# EasyEDA_Schematic.net
KiCad netlist of a schematic drawn in EasyEDA
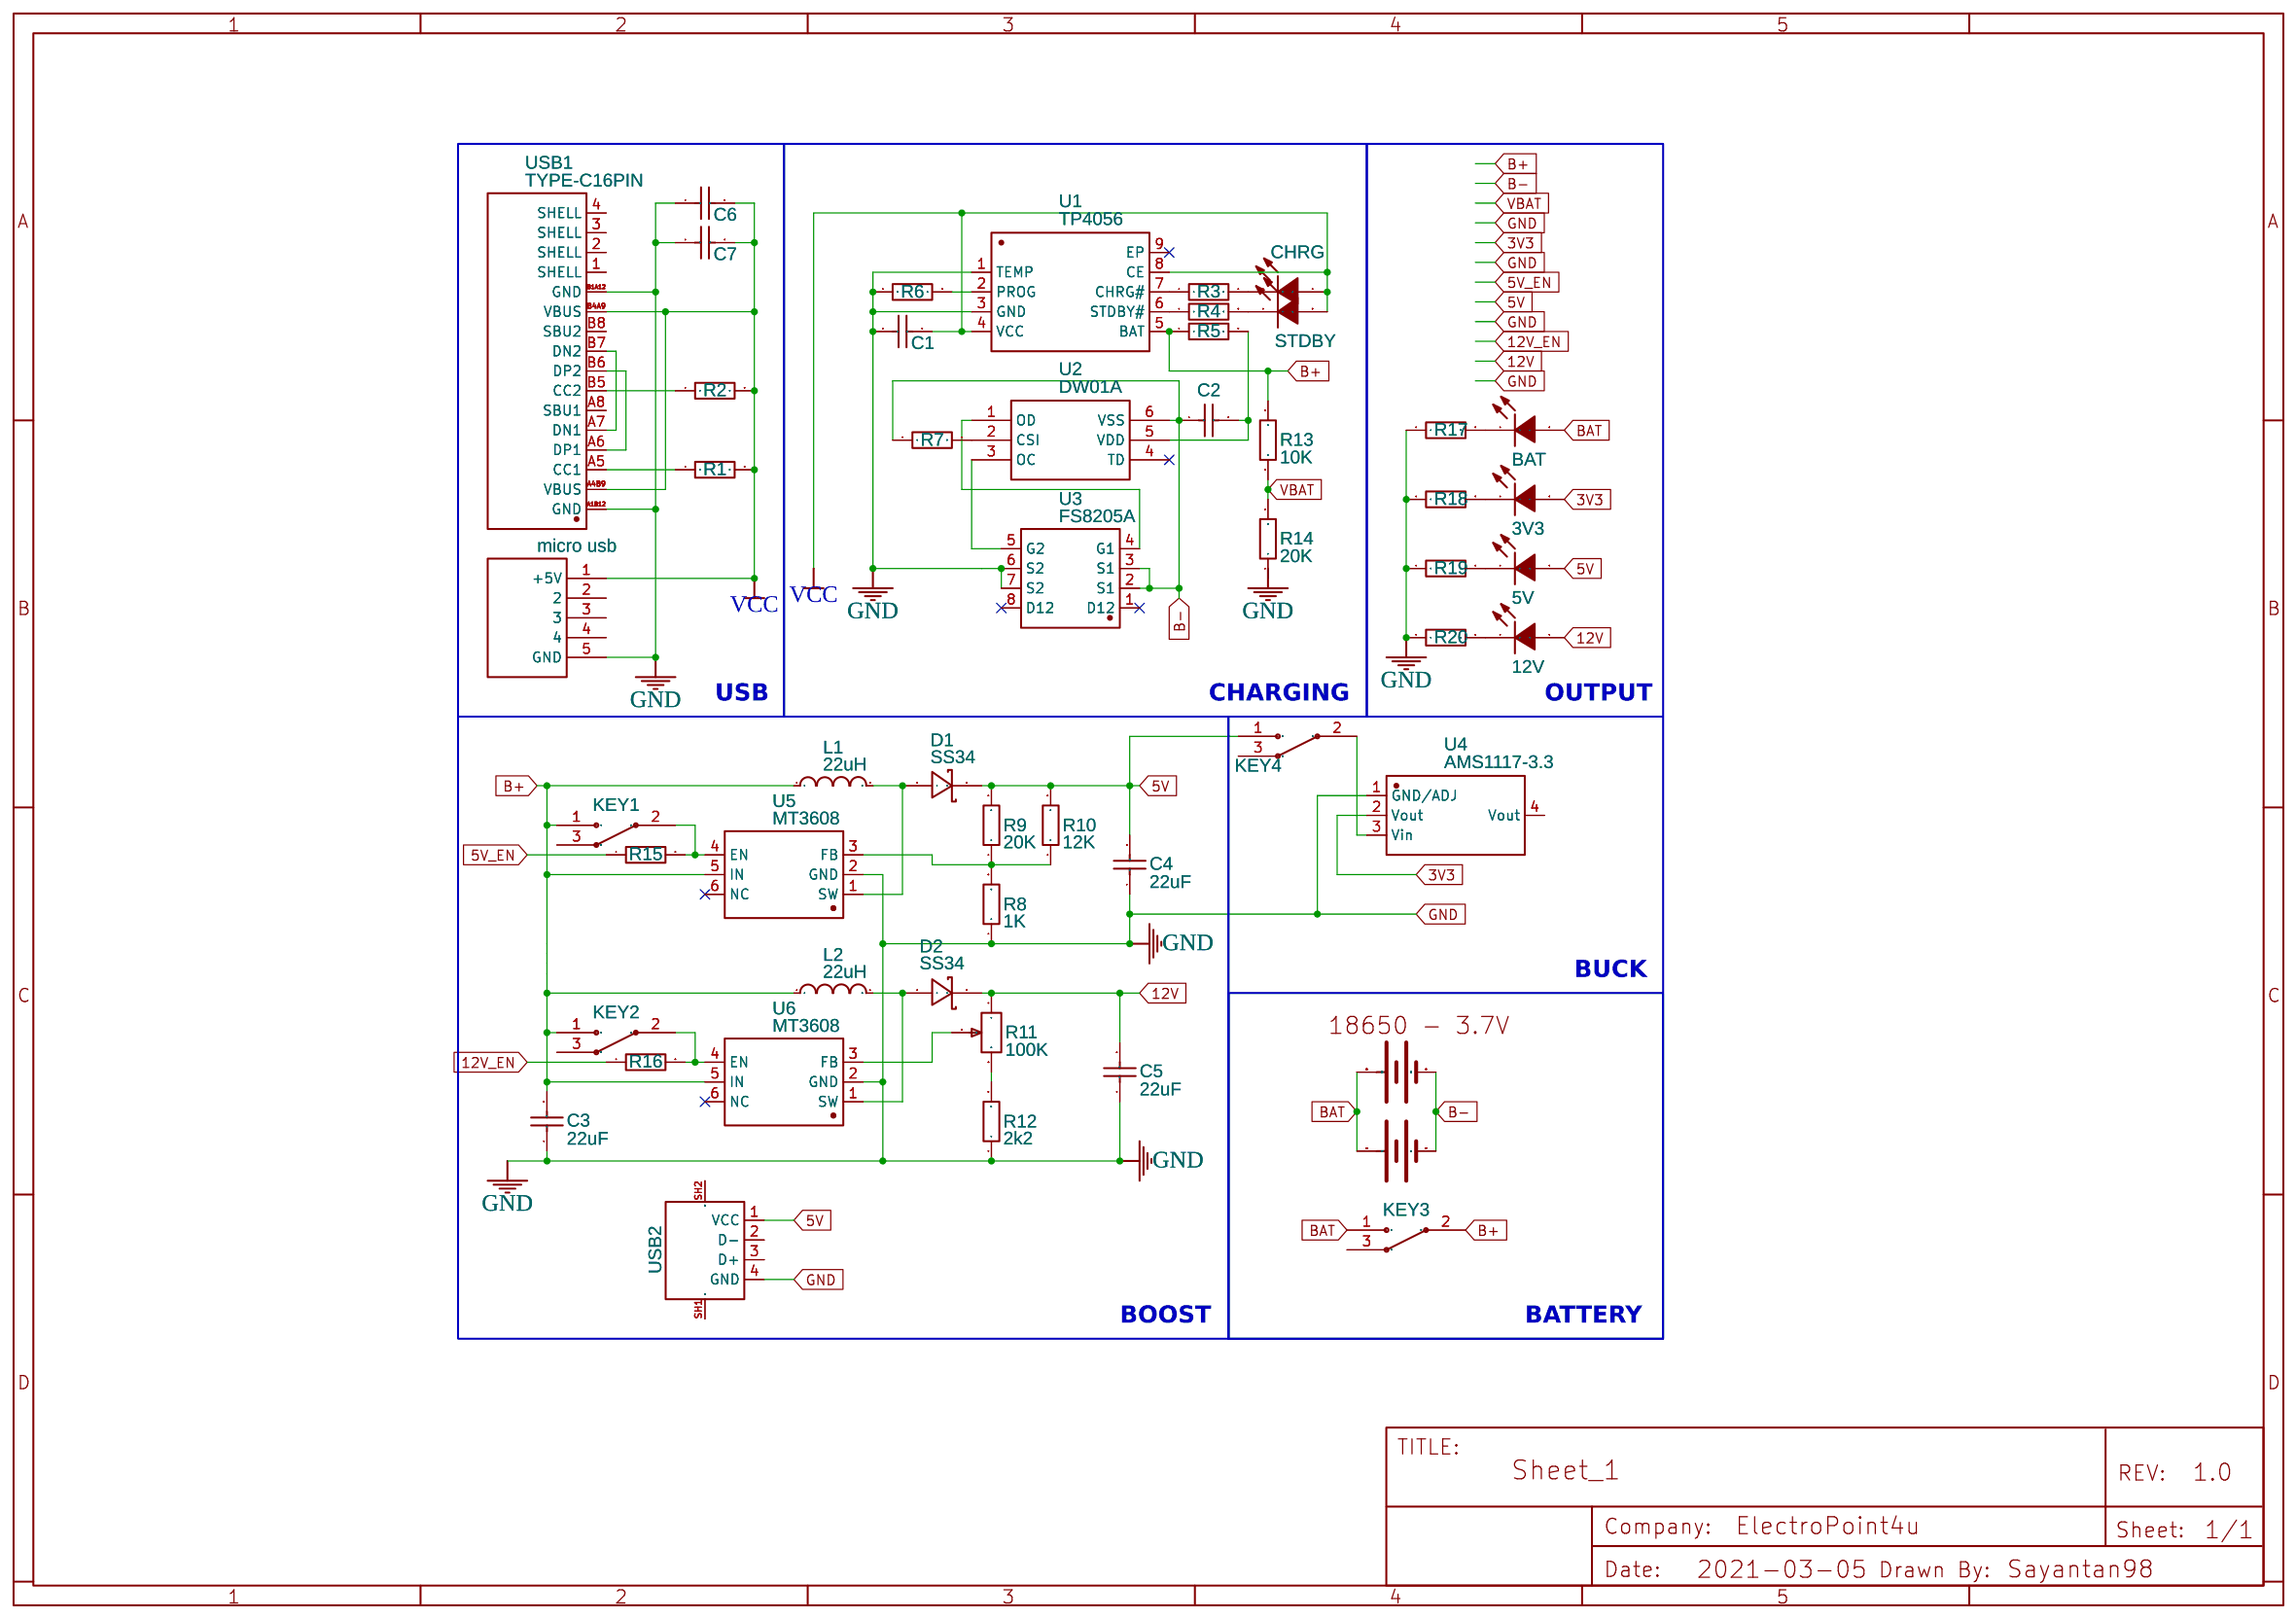
[diagram p0: schematic sheet]

(export (version "E")
  (design (tool "Eeschema 10.0.6"))
  (components
    (comp (ref "3.1V") (value "18650") (libsource (lib "") (part "18650_1")))
    (comp (ref "3.2V") (value "18650") (libsource (lib "") (part "18650")))
    (comp (ref "3V3")
      (value "0805G (Green)")
      (fields (field (name "BOM_Supplier Part") "C2297"))
      (libsource (lib "") (part "0805G (Green)_5"))
    )
    (comp (ref "5V")
      (value "0805G (Green)")
      (fields (field (name "BOM_Supplier Part") "C2297"))
      (libsource (lib "") (part "0805G (Green)_4"))
    )
    (comp (ref "12V")
      (value "0805G (Green)")
      (fields (field (name "BOM_Supplier Part") "C2297"))
      (libsource (lib "") (part "0805G (Green)"))
    )
    (comp (ref "BAT")
      (value "0805G (Green)")
      (fields (field (name "BOM_Supplier Part") "C2297"))
      (libsource (lib "") (part "0805G (Green)_2"))
    )
    (comp (ref "C1")
      (value "10uF")
      (fields
        (field (name "BOM_Manufacturer Part") "CL21A106KAYNNNE")
        (field (name "BOM_Supplier Part") "C15850")
      )
      (libsource (lib "") (part "CL21A106KAYNNNE"))
    )
    (comp (ref "C2")
      (value "100nF")
      (fields
        (field (name "BOM_Manufacturer Part") "CL21B104JBCNNNC")
        (field (name "BOM_Supplier Part") "C62912")
      )
      (libsource (lib "") (part "CL21B104JBCNNNC"))
    )
    (comp (ref "C3")
      (value "22uF")
      (fields
        (field (name "BOM_Manufacturer Part") "CL31A226KPHNNNE")
        (field (name "BOM_Supplier Part") "C5672")
      )
      (libsource (lib "") (part "CL31A226KPHNNNE"))
    )
    (comp (ref "C4")
      (value "22uF")
      (fields
        (field (name "BOM_Manufacturer Part") "CL31A226KPHNNNE")
        (field (name "BOM_Supplier Part") "C5672")
      )
      (libsource (lib "") (part "CL31A226KPHNNNE"))
    )
    (comp (ref "C5")
      (value "22uF")
      (fields
        (field (name "BOM_Manufacturer Part") "CL31A226KPHNNNE")
        (field (name "BOM_Supplier Part") "C5672")
      )
      (libsource (lib "") (part "CL31A226KPHNNNE"))
    )
    (comp (ref "C6")
      (value "10uF")
      (fields
        (field (name "BOM_Manufacturer Part") "CL21A106KAYNNNE")
        (field (name "BOM_Supplier Part") "C15850")
      )
      (libsource (lib "") (part "CL21A106KAYNNNE"))
    )
    (comp (ref "C7")
      (value "1uF")
      (fields
        (field (name "BOM_Manufacturer Part") "CL21A106KAYNNNE")
        (field (name "BOM_Supplier Part") "C15850")
      )
      (libsource (lib "") (part "CL21A106KAYNNNE"))
    )
    (comp (ref "CHRG")
      (value "0805G (Green)")
      (fields (field (name "BOM_Supplier Part") "C2297"))
      (libsource (lib "") (part "0805G (Green)_1"))
    )
    (comp (ref "D1")
      (value "SS34")
      (fields (field (name "BOM_Supplier Part") "C8678"))
      (libsource (lib "") (part "SS34_C8678"))
    )
    (comp (ref "D2")
      (value "SS34")
      (fields (field (name "BOM_Supplier Part") "C8678"))
      (libsource (lib "") (part "SS34_C8678"))
    )
    (comp (ref "KEY1")
      (value "MSK-11027 Toggle Switches")
      (fields (field (name "BOM_Supplier Part") "C21381"))
      (libsource (lib "") (part "MSK-11027 Toggle Switches"))
    )
    (comp (ref "KEY2")
      (value "MSK-11027 Toggle Switches")
      (fields (field (name "BOM_Supplier Part") "C21381"))
      (libsource (lib "") (part "MSK-11027 Toggle Switches"))
    )
    (comp (ref "KEY3")
      (value "MSK-11027 Toggle Switches")
      (fields (field (name "BOM_Supplier Part") "C21381"))
      (libsource (lib "") (part "MSK-11027 Toggle Switches"))
    )
    (comp (ref "KEY4")
      (value "MSK-11027 Toggle Switches")
      (fields (field (name "BOM_Supplier Part") "C21381"))
      (libsource (lib "") (part "MSK-11027 Toggle Switches"))
    )
    (comp (ref "L1")
      (value "22uH")
      (fields
        (field (name "BOM_Manufacturer Part") "SWRB1205S-220MT")
        (field (name "BOM_Supplier Part") "C169385")
      )
      (libsource (lib "") (part "SWRB1205S-220MT"))
    )
    (comp (ref "L2")
      (value "22uH")
      (fields
        (field (name "BOM_Manufacturer Part") "SWRB1205S-220MT")
        (field (name "BOM_Supplier Part") "C169385")
      )
      (libsource (lib "") (part "SWRB1205S-220MT"))
    )
    (comp (ref "R1")
      (value "5.1K")
      (fields
        (field (name "BOM_Manufacturer Part") "0805W8F5101T5E")
        (field (name "BOM_Supplier Part") "C27834")
      )
      (libsource (lib "") (part "0805W8F5101T5E"))
    )
    (comp (ref "R2")
      (value "5.1K")
      (fields
        (field (name "BOM_Manufacturer Part") "0805W8F5101T5E")
        (field (name "BOM_Supplier Part") "C27834")
      )
      (libsource (lib "") (part "0805W8F5101T5E"))
    )
    (comp (ref "R3")
      (value "1K")
      (fields
        (field (name "BOM_Manufacturer Part") "0805WAD1001T5E")
        (field (name "BOM_Supplier Part") "C169072")
      )
      (libsource (lib "") (part "0805WAD1001T5E"))
    )
    (comp (ref "R4")
      (value "1K")
      (fields
        (field (name "BOM_Manufacturer Part") "0805WAD1001T5E")
        (field (name "BOM_Supplier Part") "C169072")
      )
      (libsource (lib "") (part "0805WAD1001T5E"))
    )
    (comp (ref "R5")
      (value "100")
      (fields
        (field (name "BOM_Manufacturer Part") "0805W8F1000T5E")
        (field (name "BOM_Supplier Part") "C17408")
      )
      (libsource (lib "") (part "0805W8F1000T5E"))
    )
    (comp (ref "R6")
      (value "2K")
      (fields
        (field (name "BOM_Manufacturer Part") "0805W8F2001T5E")
        (field (name "BOM_Supplier Part") "C17604")
      )
      (libsource (lib "") (part "0805W8F2001T5E"))
    )
    (comp (ref "R7")
      (value "1K")
      (fields
        (field (name "BOM_Manufacturer Part") "0805WAD1001T5E")
        (field (name "BOM_Supplier Part") "C169072")
      )
      (libsource (lib "") (part "0805WAD1001T5E"))
    )
    (comp (ref "R8")
      (value "1K")
      (fields
        (field (name "BOM_Manufacturer Part") "0805W8F1001T5E")
        (field (name "BOM_Supplier Part") "C17513")
      )
      (libsource (lib "") (part "0805W8F1001T5E"))
    )
    (comp (ref "R9")
      (value "20K")
      (fields
        (field (name "BOM_Manufacturer Part") "0805W8F2002T5E")
        (field (name "BOM_Supplier Part") "C4328")
      )
      (libsource (lib "") (part "0805W8F2002T5E"))
    )
    (comp (ref "R10")
      (value "12K")
      (fields
        (field (name "BOM_Manufacturer Part") "0805W8F1202T5E")
        (field (name "BOM_Supplier Part") "C17444")
      )
      (libsource (lib "") (part "0805W8F1202T5E"))
    )
    (comp (ref "R11") (value "100K") (libsource (lib "") (part "POTENTIOMETER VARIABLE RESISTOR")))
    (comp (ref "R12")
      (value "2k2")
      (fields
        (field (name "BOM_Manufacturer Part") "0805W8F1001T5E")
        (field (name "BOM_Supplier Part") "C17513")
      )
      (libsource (lib "") (part "0805W8F1001T5E"))
    )
    (comp (ref "R13")
      (value "10K")
      (fields
        (field (name "BOM_Manufacturer Part") "TC0550B1002T5E")
        (field (name "BOM_Supplier Part") "C141888")
      )
      (libsource (lib "") (part "TC0550B1002T5E"))
    )
    (comp (ref "R14")
      (value "20K")
      (fields
        (field (name "BOM_Manufacturer Part") "TC0550B1002T5E")
        (field (name "BOM_Supplier Part") "C141888")
      )
      (libsource (lib "") (part "TC0550B1002T5E"))
    )
    (comp (ref "R15")
      (value "100")
      (fields
        (field (name "BOM_Manufacturer Part") "0805W8F1000T5E")
        (field (name "BOM_Supplier Part") "C17408")
      )
      (libsource (lib "") (part "0805W8F1000T5E"))
    )
    (comp (ref "R16")
      (value "100")
      (fields
        (field (name "BOM_Manufacturer Part") "0805W8F1000T5E")
        (field (name "BOM_Supplier Part") "C17408")
      )
      (libsource (lib "") (part "0805W8F1000T5E"))
    )
    (comp (ref "R17")
      (value "1K")
      (fields
        (field (name "BOM_Manufacturer Part") "0805WAD1001T5E")
        (field (name "BOM_Supplier Part") "C169072")
      )
      (libsource (lib "") (part "0805WAD1001T5E"))
    )
    (comp (ref "R18")
      (value "1K")
      (fields
        (field (name "BOM_Manufacturer Part") "0805WAD1001T5E")
        (field (name "BOM_Supplier Part") "C169072")
      )
      (libsource (lib "") (part "0805WAD1001T5E"))
    )
    (comp (ref "R19")
      (value "1K")
      (fields
        (field (name "BOM_Manufacturer Part") "0805WAD1001T5E")
        (field (name "BOM_Supplier Part") "C169072")
      )
      (libsource (lib "") (part "0805WAD1001T5E"))
    )
    (comp (ref "R20")
      (value "1K")
      (fields
        (field (name "BOM_Manufacturer Part") "0805WAD1001T5E")
        (field (name "BOM_Supplier Part") "C169072")
      )
      (libsource (lib "") (part "0805WAD1001T5E"))
    )
    (comp (ref "STDBY")
      (value "0805G (Green)")
      (fields (field (name "BOM_Supplier Part") "C2297"))
      (libsource (lib "") (part "0805G (Green)_3"))
    )
    (comp (ref "U1")
      (value "TP4056")
      (fields (field (name "BOM_Supplier Part") "C382139"))
      (libsource (lib "") (part "TP4056_C382139"))
    )
    (comp (ref "U2")
      (value "DW01A")
      (fields (field (name "BOM_Supplier Part") "C85680"))
      (libsource (lib "") (part "DW01A"))
    )
    (comp (ref "U3")
      (value "FS8205A")
      (fields (field (name "BOM_Supplier Part") "C16052"))
      (libsource (lib "") (part "FS8205A"))
    )
    (comp (ref "U4")
      (value "AMS1117-3.3")
      (fields (field (name "BOM_Supplier Part") "C6186"))
      (libsource (lib "") (part "AMS1117-3.3"))
    )
    (comp (ref "U5")
      (value "MT3608")
      (fields (field (name "BOM_Supplier Part") "C84817"))
      (libsource (lib "") (part "MT3608"))
    )
    (comp (ref "U6")
      (value "MT3608")
      (fields (field (name "BOM_Supplier Part") "C84817"))
      (libsource (lib "") (part "MT3608"))
    )
    (comp (ref "USB1")
      (value "TYPE-C16PIN")
      (fields (field (name "BOM_Supplier Part") "C393939"))
      (libsource (lib "") (part "TYPE-C16PIN"))
    )
    (comp (ref "USB2")
      (value "JTJ-USB-AF-08")
      (fields (field (name "BOM_Supplier Part") "C2345"))
      (libsource (lib "") (part "JTJ-USB-AF-08"))
    )
    (comp (ref "USB3") (value "micro usb") (libsource (lib "") (part "micro usb")))
  )
  (nets
    (net (code "1") (name "3V3") (class "Default")
      (node (ref "3V3") (pin "2") (pinfunction "A_2") (pintype "unspecified"))
      (node (ref "U4") (pin "2") (pinfunction "Vout_2") (pintype "unspecified"))
    )
    (net (code "2") (name "5V") (class "Default")
      (node (ref "5V") (pin "2") (pinfunction "A_2") (pintype "unspecified"))
      (node (ref "C4") (pin "2") (pinfunction "2_2") (pintype "input"))
      (node (ref "D1") (pin "1") (pinfunction "K_1") (pintype "unspecified"))
      (node (ref "KEY4") (pin "1") (pinfunction "1_1") (pintype "unspecified"))
      (node (ref "R10") (pin "2") (pinfunction "2_2") (pintype "input"))
      (node (ref "R9") (pin "2") (pinfunction "2_2") (pintype "input"))
      (node (ref "USB2") (pin "1") (pinfunction "VCC_1") (pintype "input"))
    )
    (net (code "3") (name "5V_EN") (class "Default")
      (node (ref "R15") (pin "1") (pinfunction "1_1") (pintype "input"))
    )
    (net (code "4") (name "12V") (class "Default")
      (node (ref "12V") (pin "2") (pinfunction "A_2") (pintype "unspecified"))
      (node (ref "C5") (pin "2") (pinfunction "2_2") (pintype "input"))
      (node (ref "D2") (pin "1") (pinfunction "K_1") (pintype "unspecified"))
      (node (ref "R11") (pin "1") (pinfunction "1_1") (pintype "input"))
    )
    (net (code "5") (name "12V_EN") (class "Default")
      (node (ref "R16") (pin "1") (pinfunction "1_1") (pintype "input"))
    )
    (net (code "6") (name "B+") (class "Default")
      (node (ref "C3") (pin "2") (pinfunction "2_2") (pintype "input"))
      (node (ref "KEY1") (pin "1") (pinfunction "1_1") (pintype "unspecified"))
      (node (ref "KEY2") (pin "1") (pinfunction "1_1") (pintype "unspecified"))
      (node (ref "KEY3") (pin "2") (pinfunction "2_2") (pintype "unspecified"))
      (node (ref "L1") (pin "1") (pinfunction "1_1") (pintype "unspecified"))
      (node (ref "L2") (pin "1") (pinfunction "1_1") (pintype "unspecified"))
      (node (ref "R13") (pin "2") (pinfunction "2_2") (pintype "unspecified"))
      (node (ref "R5") (pin "1") (pinfunction "1_1") (pintype "input"))
      (node (ref "U1") (pin "5") (pinfunction "BAT_5") (pintype "unspecified"))
      (node (ref "U5") (pin "5") (pinfunction "IN_5") (pintype "unspecified"))
      (node (ref "U6") (pin "5") (pinfunction "IN_5") (pintype "unspecified"))
    )
    (net (code "7") (name "B-") (class "Default")
      (node (ref "3.1V") (pin "GND") (pinfunction "GND_GND") (pintype "passive"))
      (node (ref "3.2V") (pin "GND") (pinfunction "GND_GND") (pintype "passive"))
      (node (ref "C2") (pin "1") (pinfunction "1_1") (pintype "input"))
      (node (ref "R7") (pin "1") (pinfunction "1_1") (pintype "unspecified"))
      (node (ref "U2") (pin "6") (pinfunction "VSS_6") (pintype "unspecified"))
      (node (ref "U3") (pin "2") (pinfunction "S1_2") (pintype "unspecified"))
      (node (ref "U3") (pin "3") (pinfunction "S1_3") (pintype "unspecified"))
    )
    (net (code "8") (name "BAT") (class "Default")
      (node (ref "3.1V") (pin "Positive") (pinfunction "Positive_Positive") (pintype "passive"))
      (node (ref "3.2V") (pin "Positive") (pinfunction "Positive_Positive") (pintype "passive"))
      (node (ref "BAT") (pin "2") (pinfunction "A_2") (pintype "unspecified"))
      (node (ref "KEY3") (pin "1") (pinfunction "1_1") (pintype "unspecified"))
    )
    (net (code "9") (name "GND") (class "Default")
      (node (ref "C1") (pin "1") (pinfunction "1_1") (pintype "input"))
      (node (ref "C3") (pin "1") (pinfunction "1_1") (pintype "input"))
      (node (ref "C4") (pin "1") (pinfunction "1_1") (pintype "input"))
      (node (ref "C5") (pin "1") (pinfunction "1_1") (pintype "input"))
      (node (ref "C6") (pin "1") (pinfunction "1_1") (pintype "input"))
      (node (ref "C7") (pin "1") (pinfunction "1_1") (pintype "input"))
      (node (ref "R12") (pin "1") (pinfunction "1_1") (pintype "input"))
      (node (ref "R14") (pin "1") (pinfunction "1_1") (pintype "unspecified"))
      (node (ref "R17") (pin "1") (pinfunction "1_1") (pintype "unspecified"))
      (node (ref "R18") (pin "1") (pinfunction "1_1") (pintype "unspecified"))
      (node (ref "R19") (pin "1") (pinfunction "1_1") (pintype "unspecified"))
      (node (ref "R20") (pin "1") (pinfunction "1_1") (pintype "unspecified"))
      (node (ref "R6") (pin "1") (pinfunction "1_1") (pintype "input"))
      (node (ref "R8") (pin "1") (pinfunction "1_1") (pintype "input"))
      (node (ref "U1") (pin "1") (pinfunction "TEMP_1") (pintype "unspecified"))
      (node (ref "U1") (pin "3") (pinfunction "GND_3") (pintype "unspecified"))
      (node (ref "U3") (pin "6") (pinfunction "S2_6") (pintype "unspecified"))
      (node (ref "U3") (pin "7") (pinfunction "S2_7") (pintype "unspecified"))
      (node (ref "U4") (pin "1") (pinfunction "GND/ADJ_1") (pintype "unspecified"))
      (node (ref "U5") (pin "2") (pinfunction "GND_2") (pintype "unspecified"))
      (node (ref "U6") (pin "2") (pinfunction "GND_2") (pintype "unspecified"))
      (node (ref "USB1") (pin "A1B12") (pinfunction "GND_A1B12") (pintype "unspecified"))
      (node (ref "USB1") (pin "B1A12") (pinfunction "GND_B1A12") (pintype "unspecified"))
      (node (ref "USB2") (pin "4") (pinfunction "GND_4") (pintype "input"))
      (node (ref "USB3") (pin "5") (pinfunction "GND_5") (pintype "unspecified"))
    )
    (net (code "10") (name "Net-(3V3-K)") (class "Default")
      (node (ref "3V3") (pin "1") (pinfunction "K_1") (pintype "unspecified"))
      (node (ref "R18") (pin "2") (pinfunction "2_2") (pintype "unspecified"))
    )
    (net (code "11") (name "Net-(5V-K)") (class "Default")
      (node (ref "5V") (pin "1") (pinfunction "K_1") (pintype "unspecified"))
      (node (ref "R19") (pin "2") (pinfunction "2_2") (pintype "unspecified"))
    )
    (net (code "12") (name "Net-(12V-K)") (class "Default")
      (node (ref "12V") (pin "1") (pinfunction "K_1") (pintype "unspecified"))
      (node (ref "R20") (pin "2") (pinfunction "2_2") (pintype "unspecified"))
    )
    (net (code "13") (name "Net-(BAT-K)") (class "Default")
      (node (ref "BAT") (pin "1") (pinfunction "K_1") (pintype "unspecified"))
      (node (ref "R17") (pin "2") (pinfunction "2_2") (pintype "unspecified"))
    )
    (net (code "14") (name "Net-(CHRG-K)") (class "Default")
      (node (ref "CHRG") (pin "1") (pinfunction "K_1") (pintype "unspecified"))
      (node (ref "R3") (pin "2") (pinfunction "2_2") (pintype "unspecified"))
    )
    (net (code "15") (name "Net-(D1-A)") (class "Default")
      (node (ref "D1") (pin "2") (pinfunction "A_2") (pintype "unspecified"))
      (node (ref "L1") (pin "2") (pinfunction "2_2") (pintype "unspecified"))
      (node (ref "U5") (pin "1") (pinfunction "SW_1") (pintype "unspecified"))
    )
    (net (code "16") (name "Net-(D2-A)") (class "Default")
      (node (ref "D2") (pin "2") (pinfunction "A_2") (pintype "unspecified"))
      (node (ref "L2") (pin "2") (pinfunction "2_2") (pintype "unspecified"))
      (node (ref "U6") (pin "1") (pinfunction "SW_1") (pintype "unspecified"))
    )
    (net (code "17") (name "Net-(R11-Pad3)") (class "Default")
      (node (ref "R11") (pin "3") (pinfunction "3_3") (pintype "input"))
      (node (ref "R12") (pin "2") (pinfunction "2_2") (pintype "input"))
    )
    (net (code "18") (name "Net-(STDBY-K)") (class "Default")
      (node (ref "R4") (pin "2") (pinfunction "2_2") (pintype "unspecified"))
      (node (ref "STDBY") (pin "1") (pinfunction "K_1") (pintype "unspecified"))
    )
    (net (code "19") (name "Net-(U1-CHRG#)") (class "Default")
      (node (ref "R3") (pin "1") (pinfunction "1_1") (pintype "unspecified"))
      (node (ref "U1") (pin "7") (pinfunction "CHRG#_7") (pintype "unspecified"))
    )
    (net (code "20") (name "Net-(U1-PROG)") (class "Default")
      (node (ref "R6") (pin "2") (pinfunction "2_2") (pintype "input"))
      (node (ref "U1") (pin "2") (pinfunction "PROG_2") (pintype "unspecified"))
    )
    (net (code "21") (name "Net-(U1-STDBY#)") (class "Default")
      (node (ref "R4") (pin "1") (pinfunction "1_1") (pintype "unspecified"))
      (node (ref "U1") (pin "6") (pinfunction "STDBY#_6") (pintype "unspecified"))
    )
    (net (code "22") (name "Net-(U2-CSI)") (class "Default")
      (node (ref "R7") (pin "2") (pinfunction "2_2") (pintype "unspecified"))
      (node (ref "U2") (pin "2") (pinfunction "CSI_2") (pintype "unspecified"))
    )
    (net (code "23") (name "Net-(U2-OC)") (class "Default")
      (node (ref "U2") (pin "3") (pinfunction "OC_3") (pintype "unspecified"))
      (node (ref "U3") (pin "5") (pinfunction "G2_5") (pintype "unspecified"))
    )
    (net (code "24") (name "Net-(U2-OD)") (class "Default")
      (node (ref "U2") (pin "1") (pinfunction "OD_1") (pintype "unspecified"))
      (node (ref "U3") (pin "4") (pinfunction "G1_4") (pintype "unspecified"))
    )
    (net (code "25") (name "Net-(U2-VDD)") (class "Default")
      (node (ref "C2") (pin "2") (pinfunction "2_2") (pintype "input"))
      (node (ref "R5") (pin "2") (pinfunction "2_2") (pintype "input"))
      (node (ref "U2") (pin "5") (pinfunction "VDD_5") (pintype "unspecified"))
    )
    (net (code "26") (name "Net-(U4-Vin)") (class "Default")
      (node (ref "KEY4") (pin "2") (pinfunction "2_2") (pintype "unspecified"))
      (node (ref "U4") (pin "3") (pinfunction "Vin_3") (pintype "unspecified"))
    )
    (net (code "27") (name "Net-(U5-EN)") (class "Default")
      (node (ref "KEY1") (pin "2") (pinfunction "2_2") (pintype "unspecified"))
      (node (ref "R15") (pin "2") (pinfunction "2_2") (pintype "input"))
      (node (ref "U5") (pin "4") (pinfunction "EN_4") (pintype "unspecified"))
    )
    (net (code "28") (name "Net-(U5-FB)") (class "Default")
      (node (ref "R10") (pin "1") (pinfunction "1_1") (pintype "input"))
      (node (ref "R8") (pin "2") (pinfunction "2_2") (pintype "input"))
      (node (ref "R9") (pin "1") (pinfunction "1_1") (pintype "input"))
      (node (ref "U5") (pin "3") (pinfunction "FB_3") (pintype "unspecified"))
    )
    (net (code "29") (name "Net-(U6-EN)") (class "Default")
      (node (ref "KEY2") (pin "2") (pinfunction "2_2") (pintype "unspecified"))
      (node (ref "R16") (pin "2") (pinfunction "2_2") (pintype "input"))
      (node (ref "U6") (pin "4") (pinfunction "EN_4") (pintype "unspecified"))
    )
    (net (code "30") (name "Net-(U6-FB)") (class "Default")
      (node (ref "R11") (pin "2") (pinfunction "2_2") (pintype "input"))
      (node (ref "U6") (pin "3") (pinfunction "FB_3") (pintype "unspecified"))
    )
    (net (code "31") (name "Net-(USB1-CC1)") (class "Default")
      (node (ref "R1") (pin "1") (pinfunction "1_1") (pintype "input"))
      (node (ref "USB1") (pin "A5") (pinfunction "CC1_A5") (pintype "unspecified"))
    )
    (net (code "32") (name "Net-(USB1-CC2)") (class "Default")
      (node (ref "R2") (pin "1") (pinfunction "1_1") (pintype "input"))
      (node (ref "USB1") (pin "B5") (pinfunction "CC2_B5") (pintype "unspecified"))
    )
    (net (code "33") (name "Net-(USB1-DN1)") (class "Default")
      (node (ref "USB1") (pin "A7") (pinfunction "DN1_A7") (pintype "unspecified"))
      (node (ref "USB1") (pin "B7") (pinfunction "DN2_B7") (pintype "unspecified"))
    )
    (net (code "34") (name "Net-(USB1-DP1)") (class "Default")
      (node (ref "USB1") (pin "A6") (pinfunction "DP1_A6") (pintype "unspecified"))
      (node (ref "USB1") (pin "B6") (pinfunction "DP2_B6") (pintype "unspecified"))
    )
    (net (code "35") (name "VBAT") (class "Default")
      (node (ref "R13") (pin "1") (pinfunction "1_1") (pintype "unspecified"))
      (node (ref "R14") (pin "2") (pinfunction "2_2") (pintype "unspecified"))
    )
    (net (code "36") (name "VCC") (class "Default")
      (node (ref "C1") (pin "2") (pinfunction "2_2") (pintype "input"))
      (node (ref "C6") (pin "2") (pinfunction "2_2") (pintype "input"))
      (node (ref "C7") (pin "2") (pinfunction "2_2") (pintype "input"))
      (node (ref "CHRG") (pin "2") (pinfunction "A_2") (pintype "unspecified"))
      (node (ref "R1") (pin "2") (pinfunction "2_2") (pintype "input"))
      (node (ref "R2") (pin "2") (pinfunction "2_2") (pintype "input"))
      (node (ref "STDBY") (pin "2") (pinfunction "A_2") (pintype "unspecified"))
      (node (ref "U1") (pin "4") (pinfunction "VCC_4") (pintype "unspecified"))
      (node (ref "U1") (pin "8") (pinfunction "CE_8") (pintype "unspecified"))
      (node (ref "USB1") (pin "A4B9") (pinfunction "VBUS_A4B9") (pintype "unspecified"))
      (node (ref "USB1") (pin "B4A9") (pinfunction "VBUS_B4A9") (pintype "unspecified"))
      (node (ref "USB3") (pin "1") (pinfunction "+5V_1") (pintype "unspecified"))
    )
    (net (code "37") (name "unconnected-(KEY1-Pad3)") (class "Default")
      (node (ref "KEY1") (pin "3") (pinfunction "3_3") (pintype "unspecified"))
    )
    (net (code "38") (name "unconnected-(KEY2-Pad3)") (class "Default")
      (node (ref "KEY2") (pin "3") (pinfunction "3_3") (pintype "unspecified"))
    )
    (net (code "39") (name "unconnected-(KEY3-Pad3)") (class "Default")
      (node (ref "KEY3") (pin "3") (pinfunction "3_3") (pintype "unspecified"))
    )
    (net (code "40") (name "unconnected-(KEY4-Pad3)") (class "Default")
      (node (ref "KEY4") (pin "3") (pinfunction "3_3") (pintype "unspecified"))
    )
    (net (code "41") (name "unconnected-(U1-EP-Pad9)") (class "Default")
      (node (ref "U1") (pin "9") (pinfunction "EP_9") (pintype "unspecified+no_connect"))
    )
    (net (code "42") (name "unconnected-(U2-TD-Pad4)") (class "Default")
      (node (ref "U2") (pin "4") (pinfunction "TD_4") (pintype "unspecified+no_connect"))
    )
    (net (code "43") (name "unconnected-(U3-D12-Pad1)") (class "Default")
      (node (ref "U3") (pin "1") (pinfunction "D12_1") (pintype "unspecified+no_connect"))
    )
    (net (code "44") (name "unconnected-(U3-D12-Pad8)") (class "Default")
      (node (ref "U3") (pin "8") (pinfunction "D12_8") (pintype "unspecified+no_connect"))
    )
    (net (code "45") (name "unconnected-(U4-Vout-Pad4)") (class "Default")
      (node (ref "U4") (pin "4") (pinfunction "Vout_4") (pintype "unspecified"))
    )
    (net (code "46") (name "unconnected-(U5-NC-Pad6)") (class "Default")
      (node (ref "U5") (pin "6") (pinfunction "NC_6") (pintype "unspecified+no_connect"))
    )
    (net (code "47") (name "unconnected-(U6-NC-Pad6)") (class "Default")
      (node (ref "U6") (pin "6") (pinfunction "NC_6") (pintype "unspecified+no_connect"))
    )
    (net (code "48") (name "unconnected-(USB1-SBU1-PadA8)") (class "Default")
      (node (ref "USB1") (pin "A8") (pinfunction "SBU1_A8") (pintype "unspecified"))
    )
    (net (code "49") (name "unconnected-(USB1-SBU2-PadB8)") (class "Default")
      (node (ref "USB1") (pin "B8") (pinfunction "SBU2_B8") (pintype "unspecified"))
    )
    (net (code "50") (name "unconnected-(USB1-SHELL-Pad1)") (class "Default")
      (node (ref "USB1") (pin "1") (pinfunction "SHELL_1") (pintype "unspecified"))
    )
    (net (code "51") (name "unconnected-(USB1-SHELL-Pad2)") (class "Default")
      (node (ref "USB1") (pin "2") (pinfunction "SHELL_2") (pintype "unspecified"))
    )
    (net (code "52") (name "unconnected-(USB1-SHELL-Pad3)") (class "Default")
      (node (ref "USB1") (pin "3") (pinfunction "SHELL_3") (pintype "unspecified"))
    )
    (net (code "53") (name "unconnected-(USB1-SHELL-Pad4)") (class "Default")
      (node (ref "USB1") (pin "4") (pinfunction "SHELL_4") (pintype "unspecified"))
    )
    (net (code "54") (name "unconnected-(USB2-D+-Pad3)") (class "Default")
      (node (ref "USB2") (pin "3") (pinfunction "D+_3") (pintype "input"))
    )
    (net (code "55") (name "unconnected-(USB2-D--Pad2)") (class "Default")
      (node (ref "USB2") (pin "2") (pinfunction "D-_2") (pintype "input"))
    )
    (net (code "56") (name "unconnected-(USB2-PadSH1)") (class "Default")
      (node (ref "USB2") (pin "SH1") (pinfunction "SH1_SH1") (pintype "unspecified"))
    )
    (net (code "57") (name "unconnected-(USB2-PadSH2)") (class "Default")
      (node (ref "USB2") (pin "SH2") (pinfunction "SH2_SH2") (pintype "unspecified"))
    )
    (net (code "58") (name "unconnected-(USB3-Pad2)") (class "Default")
      (node (ref "USB3") (pin "2") (pinfunction "2_2") (pintype "unspecified"))
    )
    (net (code "59") (name "unconnected-(USB3-Pad3)") (class "Default")
      (node (ref "USB3") (pin "3") (pinfunction "3_3") (pintype "unspecified"))
    )
    (net (code "60") (name "unconnected-(USB3-Pad4)") (class "Default")
      (node (ref "USB3") (pin "4") (pinfunction "4_4") (pintype "unspecified"))
    )
  )
)
